# Esp32_with_USBC.net
KiCad netlist of a schematic drawn in Altium Designer
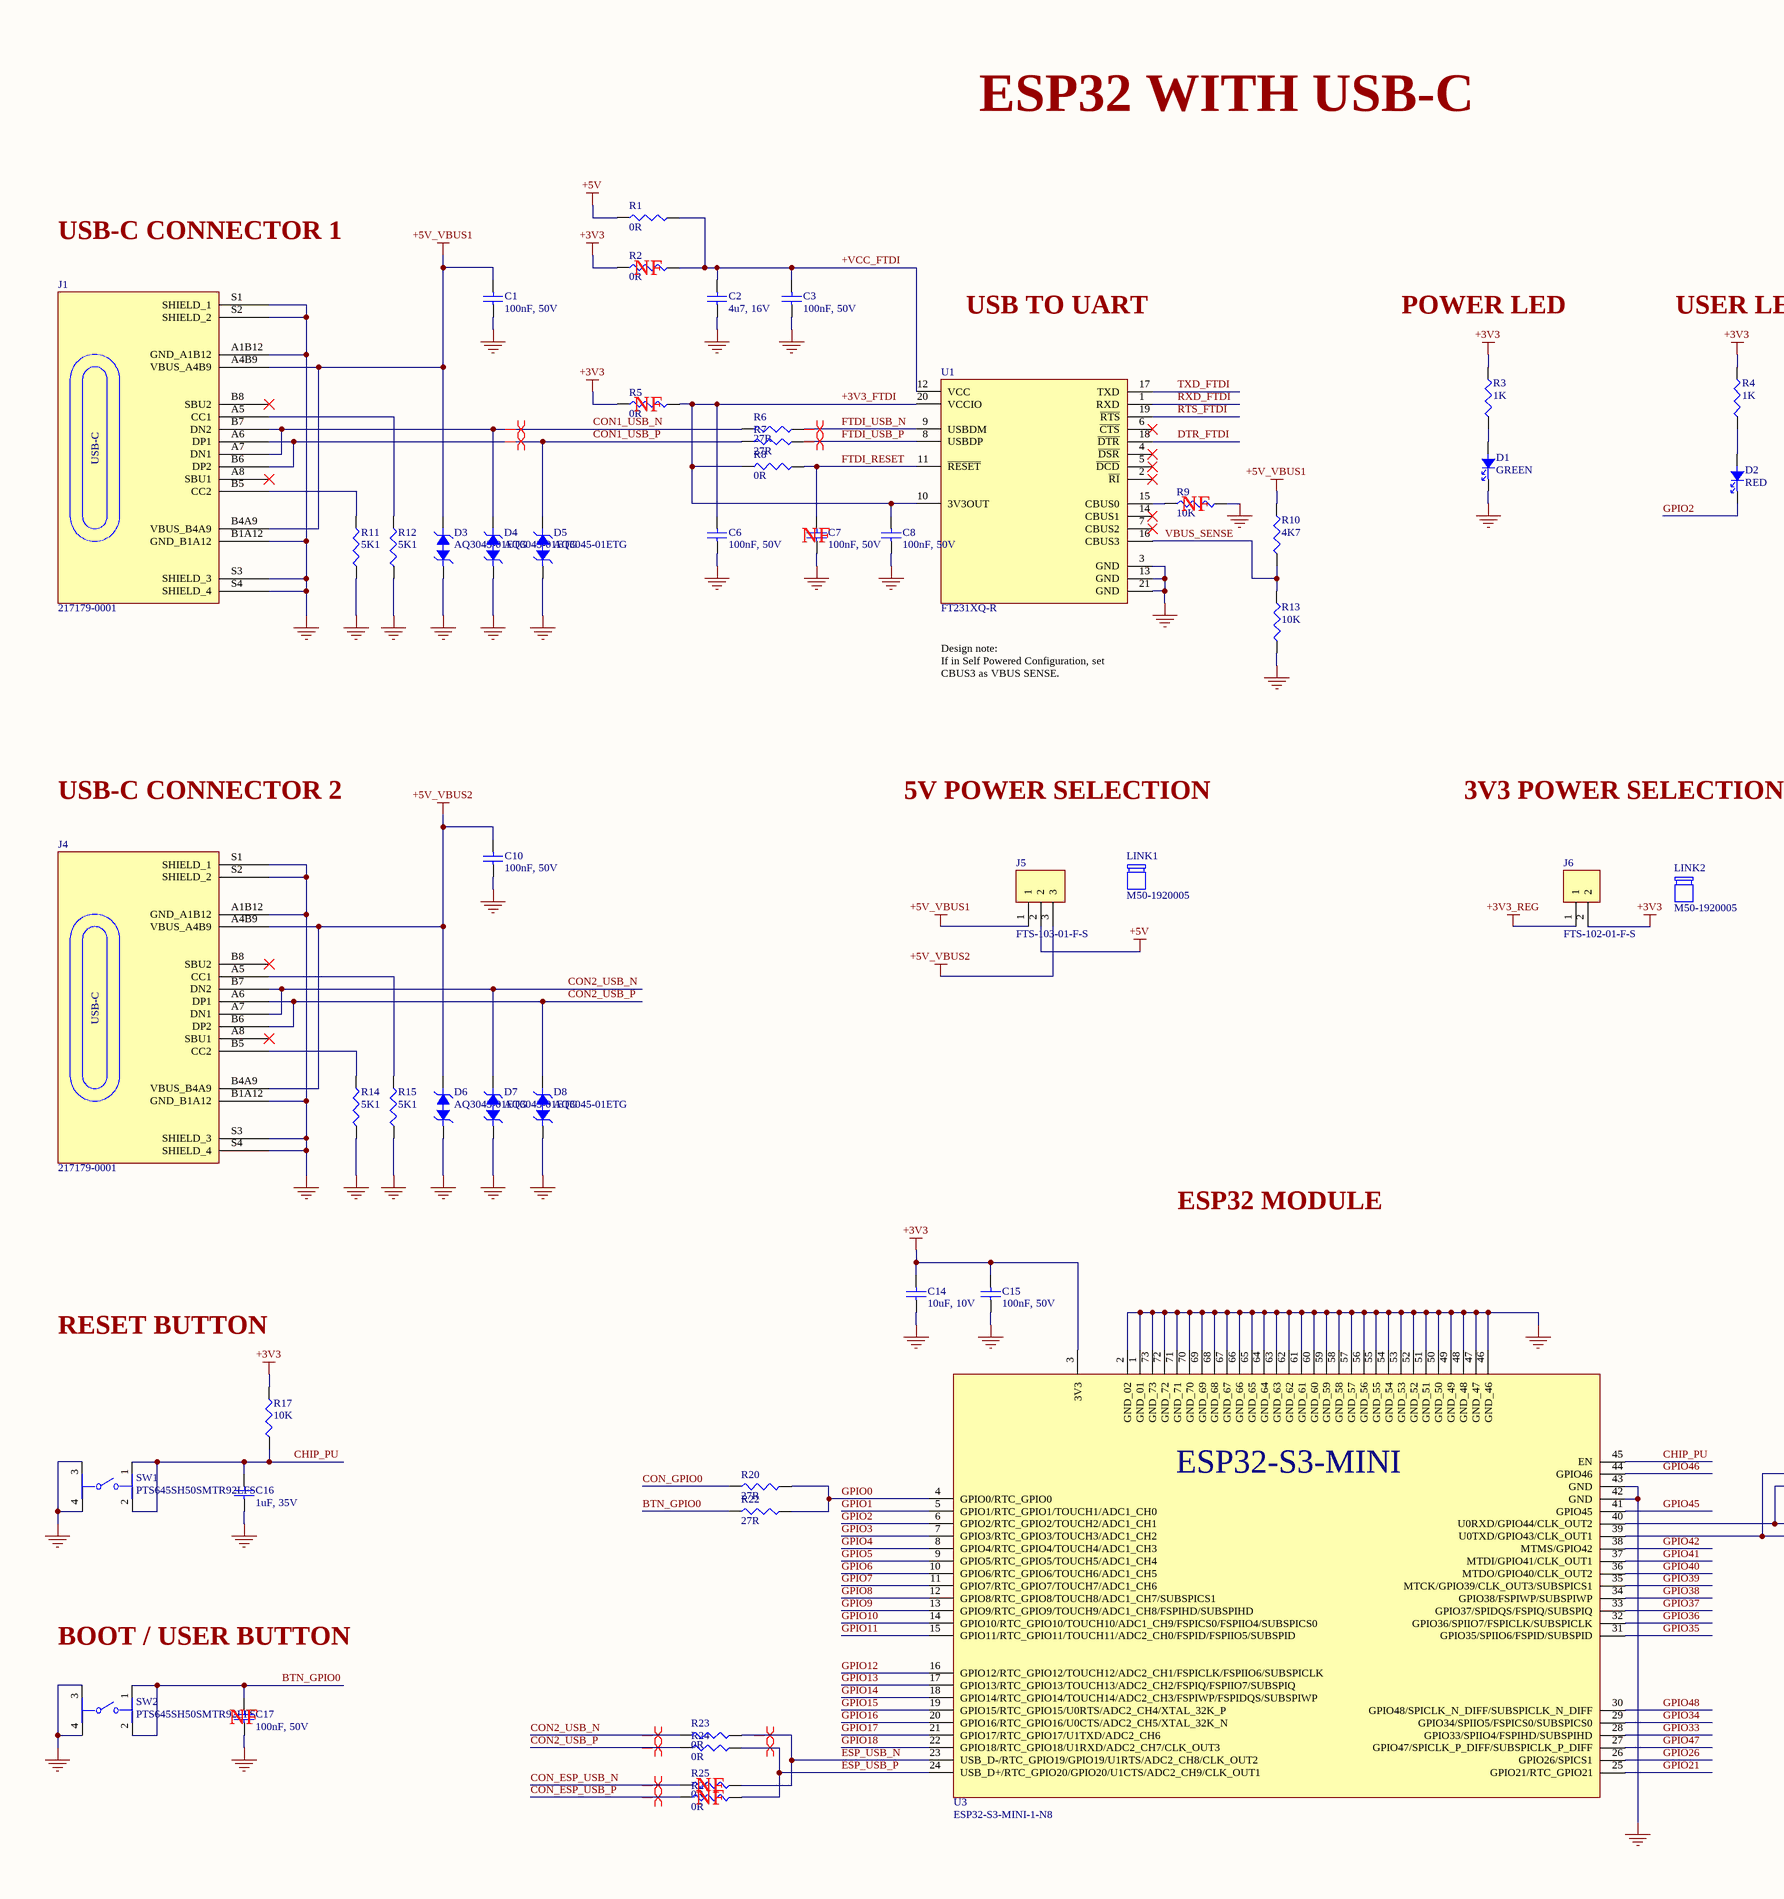
[diagram p0: Esp32 with USBC.SchDoc, left]
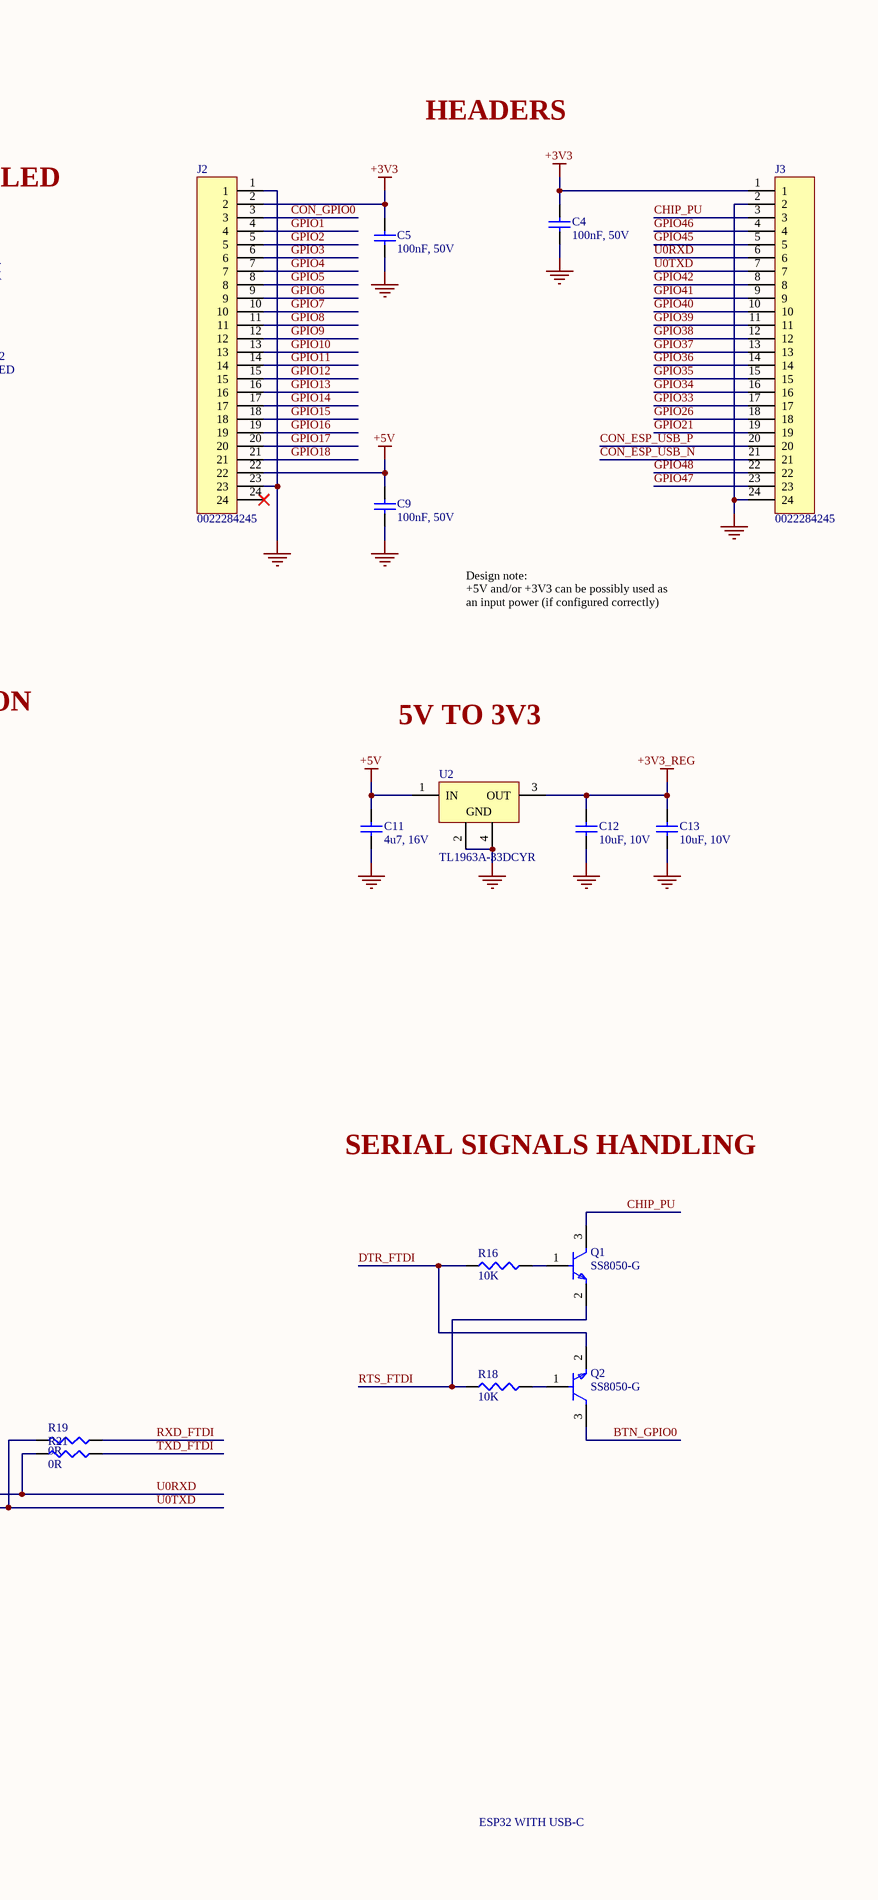
[diagram p1: Esp32 with USBC.SchDoc, right]

(export (version "E")
  (design (tool "Eeschema 10.0.6"))
  (components
    (comp (ref "C1")
      (value "100nF, 50V")
      (footprint "CAPC1005X55N")
      (description "CAP CER 0.1UF 50V X7R 0402")
      (fields
        (field (name "MANUFACTURER") "Samsung")
        (field (name "MANUFACTURER PART NUMBER") "CL05B104KB54PNC")
      )
      (libsource (lib "Schlib") (part "CL05B104KB54PNC"))
    )
    (comp (ref "C2")
      (value "4u7, 16V")
      (footprint "CAPC1005X55N")
      (description "CAP CER 4.7UF 16V X5R 0402")
      (fields
        (field (name "MANUFACTURER") "Samsung")
        (field (name "MANUFACTURER PART NUMBER") "CL05A475MO5NUNC")
      )
      (libsource (lib "Schlib") (part "CL05A475MO5NUNC"))
    )
    (comp (ref "C3")
      (value "100nF, 50V")
      (footprint "CAPC1005X55N")
      (description "CAP CER 0.1UF 50V X7R 0402")
      (fields
        (field (name "MANUFACTURER") "Samsung")
        (field (name "MANUFACTURER PART NUMBER") "CL05B104KB54PNC")
      )
      (libsource (lib "Schlib") (part "CL05B104KB54PNC"))
    )
    (comp (ref "C4")
      (value "100nF, 50V")
      (footprint "CAPC1005X55N")
      (description "CAP CER 0.1UF 50V X7R 0402")
      (fields
        (field (name "MANUFACTURER") "Samsung")
        (field (name "MANUFACTURER PART NUMBER") "CL05B104KB54PNC")
      )
      (libsource (lib "Schlib") (part "CL05B104KB54PNC"))
    )
    (comp (ref "C5")
      (value "100nF, 50V")
      (footprint "CAPC1005X55N")
      (description "CAP CER 0.1UF 50V X7R 0402")
      (fields
        (field (name "MANUFACTURER") "Samsung")
        (field (name "MANUFACTURER PART NUMBER") "CL05B104KB54PNC")
      )
      (libsource (lib "Schlib") (part "CL05B104KB54PNC"))
    )
    (comp (ref "C6")
      (value "100nF, 50V")
      (footprint "CAPC1005X55N")
      (description "CAP CER 0.1UF 50V X7R 0402")
      (fields
        (field (name "MANUFACTURER") "Samsung")
        (field (name "MANUFACTURER PART NUMBER") "CL05B104KB54PNC")
      )
      (libsource (lib "Schlib") (part "CL05B104KB54PNC"))
    )
    (comp (ref "C7")
      (value "100nF, 50V")
      (footprint "CAPC1005X55N")
      (description "CAP CER 0.1UF 50V X7R 0402")
      (fields
        (field (name "MANUFACTURER") "Samsung")
        (field (name "MANUFACTURER PART NUMBER") "CL05B104KB54PNC")
      )
      (libsource (lib "Schlib") (part "CL05B104KB54PNC"))
    )
    (comp (ref "C8")
      (value "100nF, 50V")
      (footprint "CAPC1005X55N")
      (description "CAP CER 0.1UF 50V X7R 0402")
      (fields
        (field (name "MANUFACTURER") "Samsung")
        (field (name "MANUFACTURER PART NUMBER") "CL05B104KB54PNC")
      )
      (libsource (lib "Schlib") (part "CL05B104KB54PNC"))
    )
    (comp (ref "C9")
      (value "100nF, 50V")
      (footprint "CAPC1005X55N")
      (description "CAP CER 0.1UF 50V X7R 0402")
      (fields
        (field (name "MANUFACTURER") "Samsung")
        (field (name "MANUFACTURER PART NUMBER") "CL05B104KB54PNC")
      )
      (libsource (lib "Schlib") (part "CL05B104KB54PNC"))
    )
    (comp (ref "C10")
      (value "100nF, 50V")
      (footprint "CAPC1005X55N")
      (description "CAP CER 0.1UF 50V X7R 0402")
      (fields
        (field (name "MANUFACTURER") "Samsung")
        (field (name "MANUFACTURER PART NUMBER") "CL05B104KB54PNC")
      )
      (libsource (lib "Schlib") (part "CL05B104KB54PNC"))
    )
    (comp (ref "C11")
      (value "4u7, 16V")
      (footprint "CAPC1005X55N")
      (description "CAP CER 4.7UF 16V X5R 0402")
      (fields
        (field (name "MANUFACTURER") "Samsung")
        (field (name "MANUFACTURER PART NUMBER") "CL05A475MO5NUNC")
      )
      (libsource (lib "Schlib") (part "CL05A475MO5NUNC"))
    )
    (comp (ref "C12")
      (value "10uF, 10V")
      (footprint "CAPC1005X55N")
      (description "CAP CER 10UF 10V X5R 0402")
      (fields
        (field (name "MANUFACTURER") "Samsung")
        (field (name "MANUFACTURER PART NUMBER") "CL05A106MP8NUB8")
      )
      (libsource (lib "Schlib") (part "CL05A106MP8NUB8"))
    )
    (comp (ref "C13")
      (value "10uF, 10V")
      (footprint "CAPC1005X55N")
      (description "CAP CER 10UF 10V X5R 0402")
      (fields
        (field (name "MANUFACTURER") "Samsung")
        (field (name "MANUFACTURER PART NUMBER") "CL05A106MP8NUB8")
      )
      (libsource (lib "Schlib") (part "CL05A106MP8NUB8"))
    )
    (comp (ref "C14")
      (value "10uF, 10V")
      (footprint "CAPC1005X55N")
      (description "CAP CER 10UF 10V X5R 0402")
      (fields
        (field (name "MANUFACTURER") "Samsung")
        (field (name "MANUFACTURER PART NUMBER") "CL05A106MP8NUB8")
      )
      (libsource (lib "Schlib") (part "CL05A106MP8NUB8"))
    )
    (comp (ref "C15")
      (value "100nF, 50V")
      (footprint "CAPC1005X55N")
      (description "CAP CER 0.1UF 50V X7R 0402")
      (fields
        (field (name "MANUFACTURER") "Samsung")
        (field (name "MANUFACTURER PART NUMBER") "CL05B104KB54PNC")
      )
      (libsource (lib "Schlib") (part "CL05B104KB54PNC"))
    )
    (comp (ref "C16")
      (value "1uF, 35V")
      (footprint "CAPC1005X55N")
      (description "CAP CER 1UF 35V X5R 0402")
      (fields
        (field (name "MANUFACTURER") "Samsung")
        (field (name "MANUFACTURER PART NUMBER") "CL05A105KL5NRNC")
      )
      (libsource (lib "Schlib") (part "CL05A105KL5NRNC"))
    )
    (comp (ref "C17")
      (value "100nF, 50V")
      (footprint "CAPC1005X55N")
      (description "CAP CER 0.1UF 50V X7R 0402")
      (fields
        (field (name "MANUFACTURER") "Samsung")
        (field (name "MANUFACTURER PART NUMBER") "CL05B104KB54PNC")
      )
      (libsource (lib "Schlib") (part "CL05B104KB54PNC"))
    )
    (comp (ref "D1")
      (value "GREEN")
      (footprint "LED0402G")
      (description "LED YLW-GRN 0402 SMD")
      (fields
        (field (name "MANUFACTURER") "Vishay")
        (field (name "MANUFACTURER PART NUMBER") "VLMG1500-GS08")
      )
      (libsource (lib "Schlib") (part "VLMG1500-GS08"))
    )
    (comp (ref "D2")
      (value "RED")
      (footprint "LED0402R")
      (description "LED RED 0402 SMD")
      (fields
        (field (name "MANUFACTURER") "Vishay")
        (field (name "MANUFACTURER PART NUMBER") "VLMS1500-GS08")
      )
      (libsource (lib "Schlib") (part "VLMS1500-GS08"))
    )
    (comp (ref "D3")
      (value "AQ3045-01ETG")
      (footprint "SOD882")
      (description "TVS DIODE 5.3VWM 12VC SOD882")
      (fields (field (name "MANUFACTURER") "Littelfuse") (field (name "LCSC PART NUMBER") "C3710326"))
      (libsource (lib "Schlib") (part "AQ3045-01ETG"))
    )
    (comp (ref "D4")
      (value "AQ3045-01ETG")
      (footprint "SOD882")
      (description "TVS DIODE 5.3VWM 12VC SOD882")
      (fields (field (name "MANUFACTURER") "Littelfuse") (field (name "LCSC PART NUMBER") "C3710326"))
      (libsource (lib "Schlib") (part "AQ3045-01ETG"))
    )
    (comp (ref "D5")
      (value "AQ3045-01ETG")
      (footprint "SOD882")
      (description "TVS DIODE 5.3VWM 12VC SOD882")
      (fields (field (name "MANUFACTURER") "Littelfuse") (field (name "LCSC PART NUMBER") "C3710326"))
      (libsource (lib "Schlib") (part "AQ3045-01ETG"))
    )
    (comp (ref "D6")
      (value "AQ3045-01ETG")
      (footprint "SOD882")
      (description "TVS DIODE 5.3VWM 12VC SOD882")
      (fields (field (name "MANUFACTURER") "Littelfuse") (field (name "LCSC PART NUMBER") "C3710326"))
      (libsource (lib "Schlib") (part "AQ3045-01ETG"))
    )
    (comp (ref "D7")
      (value "AQ3045-01ETG")
      (footprint "SOD882")
      (description "TVS DIODE 5.3VWM 12VC SOD882")
      (fields (field (name "MANUFACTURER") "Littelfuse") (field (name "LCSC PART NUMBER") "C3710326"))
      (libsource (lib "Schlib") (part "AQ3045-01ETG"))
    )
    (comp (ref "D8")
      (value "AQ3045-01ETG")
      (footprint "SOD882")
      (description "TVS DIODE 5.3VWM 12VC SOD882")
      (fields (field (name "MANUFACTURER") "Littelfuse") (field (name "LCSC PART NUMBER") "C3710326"))
      (libsource (lib "Schlib") (part "AQ3045-01ETG"))
    )
    (comp (ref "J1")
      (value "217179-0001")
      (footprint "FP-2171790001-MFG")
      (description "CONN RCP USB2.0 TYP C 24P SMD RA")
      (fields (field (name "MANUFACTURER") "Molex") (field (name "LCSC PART NUMBER") "C3197684"))
      (libsource (lib "Schlib") (part "217179-0001"))
    )
    (comp (ref "J2")
      (value "0022284245")
      (footprint "HDR_1X24_2.54MM")
      (description "CONN HEADER VERT 24POS 2.54MM")
      (fields (field (name "MANUFACTURER") "Molex") (field (name "LCSC PART NUMBER") "C7145888"))
      (libsource (lib "") (part "0022284245_1"))
    )
    (comp (ref "J3")
      (value "0022284245")
      (footprint "HDR_1X24_2.54MM")
      (description "CONN HEADER VERT 24POS 2.54MM")
      (fields (field (name "MANUFACTURER") "Molex") (field (name "LCSC PART NUMBER") "C7145888"))
      (libsource (lib "Schlib") (part "0022284245"))
    )
    (comp (ref "J4")
      (value "217179-0001")
      (footprint "FP-2171790001-MFG")
      (description "CONN RCP USB2.0 TYP C 24P SMD RA")
      (fields (field (name "MANUFACTURER") "Molex") (field (name "LCSC PART NUMBER") "C3197684"))
      (libsource (lib "Schlib") (part "217179-0001"))
    )
    (comp (ref "J5")
      (value "FTS-103-01-F-S")
      (footprint "HDR_1X3_1.27MM")
      (description "CONN HEADER VERT 3POS 1.27MM")
      (fields (field (name "MANUFACTURER") "Samtec") (field (name "LCSC PART NUMBER") "C3333578"))
      (libsource (lib "Schlib") (part "FTS-103-01-F-S"))
    )
    (comp (ref "J6")
      (value "FTS-102-01-F-S")
      (footprint "HDR_1X2_1.27MM")
      (description "CONN HEADER VERT 2POS 1.27MM")
      (fields (field (name "MANUFACTURER") "Samtec") (field (name "LCSC PART NUMBER") "C6045317"))
      (libsource (lib "Schlib") (part "FTS-102-01-F-S"))
    )
    (comp (ref "LINK1")
      (value "M50-1920005")
      (description "CONN SHUNT 1.27MM RED")
      (fields (field (name "MANUFACTURER") "Harwin") (field (name "LCSC PART NUMBER") "C6985646"))
      (libsource (lib "Schlib") (part "M50-1920005"))
    )
    (comp (ref "LINK2")
      (value "M50-1920005")
      (description "CONN SHUNT 1.27MM RED")
      (fields (field (name "MANUFACTURER") "Harwin") (field (name "LCSC PART NUMBER") "C6985646"))
      (libsource (lib "Schlib") (part "M50-1920005"))
    )
    (comp (ref "Q1")
      (value "SS8050-G")
      (footprint "FP-SS8050-G-IPC_B")
      (description "TRANS NPN 25V 1.5A SOT23-3")
      (fields (field (name "MANUFACTURER") "Comchip") (field (name "LCSC PART NUMBER") "C164886"))
      (libsource (lib "Schlib") (part "SS8050-G"))
    )
    (comp (ref "Q2")
      (value "SS8050-G")
      (footprint "FP-SS8050-G-IPC_B")
      (description "TRANS NPN 25V 1.5A SOT23-3")
      (fields (field (name "MANUFACTURER") "Comchip") (field (name "LCSC PART NUMBER") "C164886"))
      (libsource (lib "Schlib") (part "SS8050-G"))
    )
    (comp (ref "R1")
      (value "0R")
      (footprint "RESC1005X37N")
      (description "RES 0 OHM JUMPER 1/16W 0402")
      (fields
        (field (name "MANUFACTURER") "Yageo")
        (field (name "MANUFACTURER PART NUMBER") "RC0402JR-070RL")
      )
      (libsource (lib "Schlib") (part "RC0402JR-070RL"))
    )
    (comp (ref "R2")
      (value "0R")
      (footprint "RESC1005X37N")
      (description "RES 0 OHM JUMPER 1/16W 0402")
      (fields
        (field (name "MANUFACTURER") "Yageo")
        (field (name "MANUFACTURER PART NUMBER") "RC0402JR-070RL")
      )
      (libsource (lib "Schlib") (part "RC0402JR-070RL"))
    )
    (comp (ref "R3")
      (value "1K")
      (footprint "RESC1005X37N")
      (description "RES 1K OHM 1% 1/16W 0402")
      (fields
        (field (name "MANUFACTURER") "Yageo")
        (field (name "MANUFACTURER PART NUMBER") "RC0402FR-071KL")
      )
      (libsource (lib "Schlib") (part "RC0402FR-071KL"))
    )
    (comp (ref "R4")
      (value "1K")
      (footprint "RESC1005X37N")
      (description "RES 1K OHM 1% 1/16W 0402")
      (fields
        (field (name "MANUFACTURER") "Yageo")
        (field (name "MANUFACTURER PART NUMBER") "RC0402FR-071KL")
      )
      (libsource (lib "Schlib") (part "RC0402FR-071KL"))
    )
    (comp (ref "R5")
      (value "0R")
      (footprint "RESC1005X37N")
      (description "RES 0 OHM JUMPER 1/16W 0402")
      (fields
        (field (name "MANUFACTURER") "Yageo")
        (field (name "MANUFACTURER PART NUMBER") "RC0402JR-070RL")
      )
      (libsource (lib "Schlib") (part "RC0402JR-070RL"))
    )
    (comp (ref "R6")
      (value "27R")
      (footprint "RESC1005X37N")
      (description "RES 27 OHM 1% 1/16W 0402")
      (fields
        (field (name "MANUFACTURER") "Yageo")
        (field (name "MANUFACTURER PART NUMBER") "RC0402FR-0727RL")
      )
      (libsource (lib "Schlib") (part "RC0402FR-0727RL"))
    )
    (comp (ref "R7")
      (value "27R")
      (footprint "RESC1005X37N")
      (description "RES 27 OHM 1% 1/16W 0402")
      (fields
        (field (name "MANUFACTURER") "Yageo")
        (field (name "MANUFACTURER PART NUMBER") "RC0402FR-0727RL")
      )
      (libsource (lib "Schlib") (part "RC0402FR-0727RL"))
    )
    (comp (ref "R8")
      (value "0R")
      (footprint "RESC1005X37N")
      (description "RES 0 OHM JUMPER 1/16W 0402")
      (fields
        (field (name "MANUFACTURER") "Yageo")
        (field (name "MANUFACTURER PART NUMBER") "RC0402JR-070RL")
      )
      (libsource (lib "Schlib") (part "RC0402JR-070RL"))
    )
    (comp (ref "R9")
      (value "10K")
      (footprint "RESC1005X37N")
      (description "RES SMD 10K OHM 1% 1/16W 0402")
      (fields
        (field (name "MANUFACTURER") "Yageo")
        (field (name "MANUFACTURER PART NUMBER") "AC0402FR-0710KL")
      )
      (libsource (lib "Schlib") (part "AC0402FR-0710KL"))
    )
    (comp (ref "R10")
      (value "4K7")
      (footprint "RESC1005X37N")
      (description "RES 4.7K OHM 1% 1/16W 0402")
      (fields
        (field (name "MANUFACTURER") "Yageo")
        (field (name "MANUFACTURER PART NUMBER") "RC0402FR-074K7L")
      )
      (libsource (lib "Schlib") (part "RC0402FR-074K7L"))
    )
    (comp (ref "R11")
      (value "5K1")
      (footprint "RESC1005X37N")
      (description "RES SMD 5.1K OHM 1% 1/16W 0402")
      (fields
        (field (name "MANUFACTURER") "Yageo")
        (field (name "MANUFACTURER PART NUMBER") "AC0402FR-075K1L")
      )
      (libsource (lib "Schlib") (part "AC0402FR-075K1L"))
    )
    (comp (ref "R12")
      (value "5K1")
      (footprint "RESC1005X37N")
      (description "RES SMD 5.1K OHM 1% 1/16W 0402")
      (fields
        (field (name "MANUFACTURER") "Yageo")
        (field (name "MANUFACTURER PART NUMBER") "AC0402FR-075K1L")
      )
      (libsource (lib "Schlib") (part "AC0402FR-075K1L"))
    )
    (comp (ref "R13")
      (value "10K")
      (footprint "RESC1005X37N")
      (description "RES SMD 10K OHM 1% 1/16W 0402")
      (fields
        (field (name "MANUFACTURER") "Yageo")
        (field (name "MANUFACTURER PART NUMBER") "AC0402FR-0710KL")
      )
      (libsource (lib "Schlib") (part "AC0402FR-0710KL"))
    )
    (comp (ref "R14")
      (value "5K1")
      (footprint "RESC1005X37N")
      (description "RES SMD 5.1K OHM 1% 1/16W 0402")
      (fields
        (field (name "MANUFACTURER") "Yageo")
        (field (name "MANUFACTURER PART NUMBER") "AC0402FR-075K1L")
      )
      (libsource (lib "Schlib") (part "AC0402FR-075K1L"))
    )
    (comp (ref "R15")
      (value "5K1")
      (footprint "RESC1005X37N")
      (description "RES SMD 5.1K OHM 1% 1/16W 0402")
      (fields
        (field (name "MANUFACTURER") "Yageo")
        (field (name "MANUFACTURER PART NUMBER") "AC0402FR-075K1L")
      )
      (libsource (lib "Schlib") (part "AC0402FR-075K1L"))
    )
    (comp (ref "R16")
      (value "10K")
      (footprint "RESC1005X37N")
      (description "RES SMD 10K OHM 1% 1/16W 0402")
      (fields
        (field (name "MANUFACTURER") "Yageo")
        (field (name "MANUFACTURER PART NUMBER") "AC0402FR-0710KL")
      )
      (libsource (lib "Schlib") (part "AC0402FR-0710KL"))
    )
    (comp (ref "R17")
      (value "10K")
      (footprint "RESC1005X37N")
      (description "RES SMD 10K OHM 1% 1/16W 0402")
      (fields
        (field (name "MANUFACTURER") "Yageo")
        (field (name "MANUFACTURER PART NUMBER") "AC0402FR-0710KL")
      )
      (libsource (lib "Schlib") (part "AC0402FR-0710KL"))
    )
    (comp (ref "R18")
      (value "10K")
      (footprint "RESC1005X37N")
      (description "RES SMD 10K OHM 1% 1/16W 0402")
      (fields
        (field (name "MANUFACTURER") "Yageo")
        (field (name "MANUFACTURER PART NUMBER") "AC0402FR-0710KL")
      )
      (libsource (lib "Schlib") (part "AC0402FR-0710KL"))
    )
    (comp (ref "R19")
      (value "0R")
      (footprint "RESC1005X37N")
      (description "RES 0 OHM JUMPER 1/16W 0402")
      (fields
        (field (name "MANUFACTURER") "Yageo")
        (field (name "MANUFACTURER PART NUMBER") "RC0402JR-070RL")
      )
      (libsource (lib "Schlib") (part "RC0402JR-070RL"))
    )
    (comp (ref "R20")
      (value "27R")
      (footprint "RESC1005X37N")
      (description "RES 27 OHM 1% 1/16W 0402")
      (fields
        (field (name "MANUFACTURER") "Yageo")
        (field (name "MANUFACTURER PART NUMBER") "RC0402FR-0727RL")
      )
      (libsource (lib "Schlib") (part "RC0402FR-0727RL"))
    )
    (comp (ref "R21")
      (value "0R")
      (footprint "RESC1005X37N")
      (description "RES 0 OHM JUMPER 1/16W 0402")
      (fields
        (field (name "MANUFACTURER") "Yageo")
        (field (name "MANUFACTURER PART NUMBER") "RC0402JR-070RL")
      )
      (libsource (lib "Schlib") (part "RC0402JR-070RL"))
    )
    (comp (ref "R22")
      (value "27R")
      (footprint "RESC1005X37N")
      (description "RES 27 OHM 1% 1/16W 0402")
      (fields
        (field (name "MANUFACTURER") "Yageo")
        (field (name "MANUFACTURER PART NUMBER") "RC0402FR-0727RL")
      )
      (libsource (lib "Schlib") (part "RC0402FR-0727RL"))
    )
    (comp (ref "R23")
      (value "0R")
      (footprint "RESC1005X37N")
      (description "RES 0 OHM JUMPER 1/16W 0402")
      (fields
        (field (name "MANUFACTURER") "Yageo")
        (field (name "MANUFACTURER PART NUMBER") "RC0402JR-070RL")
      )
      (libsource (lib "Schlib") (part "RC0402JR-070RL"))
    )
    (comp (ref "R24")
      (value "0R")
      (footprint "RESC1005X37N")
      (description "RES 0 OHM JUMPER 1/16W 0402")
      (fields
        (field (name "MANUFACTURER") "Yageo")
        (field (name "MANUFACTURER PART NUMBER") "RC0402JR-070RL")
      )
      (libsource (lib "Schlib") (part "RC0402JR-070RL"))
    )
    (comp (ref "R25")
      (value "0R")
      (footprint "RESC1005X37N")
      (description "RES 0 OHM JUMPER 1/16W 0402")
      (fields
        (field (name "MANUFACTURER") "Yageo")
        (field (name "MANUFACTURER PART NUMBER") "RC0402JR-070RL")
      )
      (libsource (lib "Schlib") (part "RC0402JR-070RL"))
    )
    (comp (ref "R26")
      (value "0R")
      (footprint "RESC1005X37N")
      (description "RES 0 OHM JUMPER 1/16W 0402")
      (fields
        (field (name "MANUFACTURER") "Yageo")
        (field (name "MANUFACTURER PART NUMBER") "RC0402JR-070RL")
      )
      (libsource (lib "Schlib") (part "RC0402JR-070RL"))
    )
    (comp (ref "SW1")
      (value "PTS645SH50SMTR92LFS")
      (footprint "FP-PTS645SH50SMTR92LFS-MFG")
      (description "SWITCH TACTILE SPST-NO 0.05A 12V")
      (fields (field (name "MANUFACTURER") "ITT C&K") (field (name "LCSC PART NUMBER") "C221869"))
      (libsource (lib "Schlib") (part "PTS645SH50SMTR92LFS"))
    )
    (comp (ref "SW2")
      (value "PTS645SH50SMTR92LFS")
      (footprint "FP-PTS645SH50SMTR92LFS-MFG")
      (description "SWITCH TACTILE SPST-NO 0.05A 12V")
      (fields (field (name "MANUFACTURER") "ITT C&K") (field (name "LCSC PART NUMBER") "C221869"))
      (libsource (lib "Schlib") (part "PTS645SH50SMTR92LFS"))
    )
    (comp (ref "U1")
      (value "FT231XQ-R")
      (footprint "FP-QFN-20-IPC_B")
      (description "IC USB SERIAL FULL UART 20QFN")
      (fields (field (name "MANUFACTURER") "FTDI") (field (name "LCSC PART NUMBER") "C132159"))
      (libsource (lib "Schlib") (part "FT231XQ-R"))
    )
    (comp (ref "U2")
      (value "TL1963A-33DCYR")
      (footprint "DCY0004A_N")
      (description "IC REG LINEAR 3.3V 1.5A SOT223-4")
      (fields (field (name "MANUFACTURER") "Texas Instruments") (field (name "LCSC PART NUMBER") "C181262"))
      (libsource (lib "Schlib") (part "TL1963A-33DCYR"))
    )
    (comp (ref "U3")
      (value "ESP32-S3-MINI-1-N8")
      (footprint "XCVR_ESP32-S3-MINI-1-N8")
      (description "SMD Module, ESP32-S3FN8, 8 mb Sp")
      (fields (field (name "MANUFACTURER") "Espressif Systems") (field (name "LCSC PART NUMBER") "C2913206"))
      (libsource (lib "Schlib") (part "ESP32-S3-MINI-1-N8"))
    )
  )
  (nets
    (net (code "1") (name "+3V3") (class "Default")
      (node (ref "C14") (pin "2") (pinfunction "2_2") (pintype "passive"))
      (node (ref "C15") (pin "2") (pinfunction "2_2") (pintype "passive"))
      (node (ref "C4") (pin "2") (pinfunction "2_2") (pintype "passive"))
      (node (ref "C5") (pin "2") (pinfunction "2_2") (pintype "passive"))
      (node (ref "J2") (pin "2") (pinfunction "2_2") (pintype "passive"))
      (node (ref "J3") (pin "1") (pinfunction "1_1") (pintype "passive"))
      (node (ref "J6") (pin "2") (pinfunction "2_2") (pintype "passive"))
      (node (ref "R17") (pin "2") (pinfunction "2_2") (pintype "passive"))
      (node (ref "R2") (pin "1") (pinfunction "1_1") (pintype "passive"))
      (node (ref "R3") (pin "2") (pinfunction "2_2") (pintype "passive"))
      (node (ref "R4") (pin "2") (pinfunction "2_2") (pintype "passive"))
      (node (ref "R5") (pin "1") (pinfunction "1_1") (pintype "passive"))
      (node (ref "U3") (pin "3") (pinfunction "3V3_3") (pintype "passive"))
    )
    (net (code "2") (name "+3V3_REG") (class "Default")
      (node (ref "C12") (pin "2") (pinfunction "2_2") (pintype "passive"))
      (node (ref "C13") (pin "2") (pinfunction "2_2") (pintype "passive"))
      (node (ref "J6") (pin "1") (pinfunction "1_1") (pintype "passive"))
      (node (ref "U2") (pin "3") (pinfunction "OUT_3") (pintype "power_in"))
    )
    (net (code "3") (name "+5V") (class "Default")
      (node (ref "C11") (pin "2") (pinfunction "2_2") (pintype "passive"))
      (node (ref "C9") (pin "2") (pinfunction "2_2") (pintype "passive"))
      (node (ref "J2") (pin "22") (pinfunction "22_22") (pintype "passive"))
      (node (ref "J5") (pin "2") (pinfunction "2_2") (pintype "passive"))
      (node (ref "R1") (pin "1") (pinfunction "1_1") (pintype "passive"))
      (node (ref "U2") (pin "1") (pinfunction "IN_1") (pintype "power_in"))
    )
    (net (code "4") (name "+5V_VBUS1") (class "Default")
      (node (ref "C1") (pin "2") (pinfunction "2_2") (pintype "passive"))
      (node (ref "D3") (pin "2") (pinfunction "2_2") (pintype "passive"))
      (node (ref "J1") (pin "A4B9") (pinfunction "VBUS_A4B9_A4B9") (pintype "passive"))
      (node (ref "J1") (pin "B4A9") (pinfunction "VBUS_B4A9_B4A9") (pintype "passive"))
      (node (ref "J5") (pin "1") (pinfunction "1_1") (pintype "passive"))
      (node (ref "R10") (pin "2") (pinfunction "2_2") (pintype "passive"))
    )
    (net (code "5") (name "+5V_VBUS2") (class "Default")
      (node (ref "C10") (pin "2") (pinfunction "2_2") (pintype "passive"))
      (node (ref "D6") (pin "2") (pinfunction "2_2") (pintype "passive"))
      (node (ref "J4") (pin "A4B9") (pinfunction "VBUS_A4B9_A4B9") (pintype "passive"))
      (node (ref "J4") (pin "B4A9") (pinfunction "VBUS_B4A9_B4A9") (pintype "passive"))
      (node (ref "J5") (pin "3") (pinfunction "3_3") (pintype "passive"))
    )
    (net (code "6") (name "/+3V3_FTDI") (class "Default")
      (node (ref "C6") (pin "2") (pinfunction "2_2") (pintype "passive"))
      (node (ref "C8") (pin "2") (pinfunction "2_2") (pintype "passive"))
      (node (ref "R5") (pin "2") (pinfunction "2_2") (pintype "passive"))
      (node (ref "R8") (pin "1") (pinfunction "1_1") (pintype "passive"))
      (node (ref "U1") (pin "10") (pinfunction "3V3OUT_10") (pintype "passive"))
      (node (ref "U1") (pin "20") (pinfunction "VCCIO_20") (pintype "passive"))
    )
    (net (code "7") (name "/+VCC_FTDI") (class "Default")
      (node (ref "C2") (pin "2") (pinfunction "2_2") (pintype "passive"))
      (node (ref "C3") (pin "2") (pinfunction "2_2") (pintype "passive"))
      (node (ref "R1") (pin "2") (pinfunction "2_2") (pintype "passive"))
      (node (ref "R2") (pin "2") (pinfunction "2_2") (pintype "passive"))
      (node (ref "U1") (pin "12") (pinfunction "VCC_12") (pintype "passive"))
    )
    (net (code "8") (name "/BTN_GPIO0") (class "Default")
      (node (ref "C17") (pin "2") (pinfunction "2_2") (pintype "passive"))
      (node (ref "Q2") (pin "3") (pinfunction "C_3") (pintype "passive"))
      (node (ref "R22") (pin "1") (pinfunction "1_1") (pintype "passive"))
      (node (ref "SW2") (pin "1") (pinfunction "1_1") (pintype "passive"))
      (node (ref "SW2") (pin "2") (pinfunction "2_2") (pintype "passive"))
    )
    (net (code "9") (name "/CHIP_PU") (class "Default")
      (node (ref "C16") (pin "2") (pinfunction "2_2") (pintype "passive"))
      (node (ref "J3") (pin "3") (pinfunction "3_3") (pintype "passive"))
      (node (ref "Q1") (pin "3") (pinfunction "C_3") (pintype "passive"))
      (node (ref "R17") (pin "1") (pinfunction "1_1") (pintype "passive"))
      (node (ref "SW1") (pin "1") (pinfunction "1_1") (pintype "passive"))
      (node (ref "SW1") (pin "2") (pinfunction "2_2") (pintype "passive"))
      (node (ref "U3") (pin "45") (pinfunction "EN_45") (pintype "passive"))
    )
    (net (code "10") (name "/CON1_USB_N") (class "Default")
      (node (ref "D4") (pin "2") (pinfunction "2_2") (pintype "passive"))
      (node (ref "J1") (pin "A7") (pinfunction "DN1_A7") (pintype "passive"))
      (node (ref "J1") (pin "B7") (pinfunction "DN2_B7") (pintype "passive"))
      (node (ref "R6") (pin "1") (pinfunction "1_1") (pintype "passive"))
    )
    (net (code "11") (name "/CON1_USB_P") (class "Default")
      (node (ref "D5") (pin "2") (pinfunction "2_2") (pintype "passive"))
      (node (ref "J1") (pin "A6") (pinfunction "DP1_A6") (pintype "passive"))
      (node (ref "J1") (pin "B6") (pinfunction "DP2_B6") (pintype "passive"))
      (node (ref "R7") (pin "1") (pinfunction "1_1") (pintype "passive"))
    )
    (net (code "12") (name "/CON2_USB_N") (class "Default")
      (node (ref "D7") (pin "2") (pinfunction "2_2") (pintype "passive"))
      (node (ref "J4") (pin "A7") (pinfunction "DN1_A7") (pintype "passive"))
      (node (ref "J4") (pin "B7") (pinfunction "DN2_B7") (pintype "passive"))
      (node (ref "R23") (pin "1") (pinfunction "1_1") (pintype "passive"))
    )
    (net (code "13") (name "/CON2_USB_P") (class "Default")
      (node (ref "D8") (pin "2") (pinfunction "2_2") (pintype "passive"))
      (node (ref "J4") (pin "A6") (pinfunction "DP1_A6") (pintype "passive"))
      (node (ref "J4") (pin "B6") (pinfunction "DP2_B6") (pintype "passive"))
      (node (ref "R24") (pin "1") (pinfunction "1_1") (pintype "passive"))
    )
    (net (code "14") (name "/CON_ESP_USB_N") (class "Default")
      (node (ref "J3") (pin "21") (pinfunction "21_21") (pintype "passive"))
      (node (ref "R25") (pin "1") (pinfunction "1_1") (pintype "passive"))
    )
    (net (code "15") (name "/CON_ESP_USB_P") (class "Default")
      (node (ref "J3") (pin "20") (pinfunction "20_20") (pintype "passive"))
      (node (ref "R26") (pin "1") (pinfunction "1_1") (pintype "passive"))
    )
    (net (code "16") (name "/CON_GPIO0") (class "Default")
      (node (ref "J2") (pin "3") (pinfunction "3_3") (pintype "passive"))
      (node (ref "R20") (pin "1") (pinfunction "1_1") (pintype "passive"))
    )
    (net (code "17") (name "/DTR_FTDI") (class "Default")
      (node (ref "Q2") (pin "2") (pinfunction "E_2") (pintype "passive"))
      (node (ref "R16") (pin "1") (pinfunction "1_1") (pintype "passive"))
      (node (ref "U1") (pin "18") (pinfunction "~{DTR}_18") (pintype "passive"))
    )
    (net (code "18") (name "/ESP_USB_N") (class "Default")
      (node (ref "R23") (pin "2") (pinfunction "2_2") (pintype "passive"))
      (node (ref "R25") (pin "2") (pinfunction "2_2") (pintype "passive"))
      (node (ref "U3") (pin "23") (pinfunction "USB_D-/RTC_GPIO19/GPIO19/U1RTS/ADC2_CH8/CLK_OUT2_23") (pintype "passive"))
    )
    (net (code "19") (name "/ESP_USB_P") (class "Default")
      (node (ref "R24") (pin "2") (pinfunction "2_2") (pintype "passive"))
      (node (ref "R26") (pin "2") (pinfunction "2_2") (pintype "passive"))
      (node (ref "U3") (pin "24") (pinfunction "USB_D+/RTC_GPIO20/GPIO20/U1CTS/ADC2_CH9/CLK_OUT1_24") (pintype "passive"))
    )
    (net (code "20") (name "/FTDI_RESET") (class "Default")
      (node (ref "C7") (pin "2") (pinfunction "2_2") (pintype "passive"))
      (node (ref "R8") (pin "2") (pinfunction "2_2") (pintype "passive"))
      (node (ref "U1") (pin "11") (pinfunction "~{RESET}_11") (pintype "passive"))
    )
    (net (code "21") (name "/FTDI_USB_N") (class "Default")
      (node (ref "R6") (pin "2") (pinfunction "2_2") (pintype "passive"))
      (node (ref "U1") (pin "9") (pinfunction "USBDM_9") (pintype "passive"))
    )
    (net (code "22") (name "/FTDI_USB_P") (class "Default")
      (node (ref "R7") (pin "2") (pinfunction "2_2") (pintype "passive"))
      (node (ref "U1") (pin "8") (pinfunction "USBDP_8") (pintype "passive"))
    )
    (net (code "23") (name "/GPIO0") (class "Default")
      (node (ref "R20") (pin "2") (pinfunction "2_2") (pintype "passive"))
      (node (ref "R22") (pin "2") (pinfunction "2_2") (pintype "passive"))
      (node (ref "U3") (pin "4") (pinfunction "GPIO0/RTC_GPIO0_4") (pintype "passive"))
    )
    (net (code "24") (name "/GPIO1") (class "Default")
      (node (ref "J2") (pin "4") (pinfunction "4_4") (pintype "passive"))
      (node (ref "U3") (pin "5") (pinfunction "GPIO1/RTC_GPIO1/TOUCH1/ADC1_CH0_5") (pintype "passive"))
    )
    (net (code "25") (name "/GPIO2") (class "Default")
      (node (ref "D2") (pin "1") (pinfunction "1_1") (pintype "passive"))
      (node (ref "J2") (pin "5") (pinfunction "5_5") (pintype "passive"))
      (node (ref "U3") (pin "6") (pinfunction "GPIO2/RTC_GPIO2/TOUCH2/ADC1_CH1_6") (pintype "passive"))
    )
    (net (code "26") (name "/GPIO3") (class "Default")
      (node (ref "J2") (pin "6") (pinfunction "6_6") (pintype "passive"))
      (node (ref "U3") (pin "7") (pinfunction "GPIO3/RTC_GPIO3/TOUCH3/ADC1_CH2_7") (pintype "passive"))
    )
    (net (code "27") (name "/GPIO4") (class "Default")
      (node (ref "J2") (pin "7") (pinfunction "7_7") (pintype "passive"))
      (node (ref "U3") (pin "8") (pinfunction "GPIO4/RTC_GPIO4/TOUCH4/ADC1_CH3_8") (pintype "passive"))
    )
    (net (code "28") (name "/GPIO5") (class "Default")
      (node (ref "J2") (pin "8") (pinfunction "8_8") (pintype "passive"))
      (node (ref "U3") (pin "9") (pinfunction "GPIO5/RTC_GPIO5/TOUCH5/ADC1_CH4_9") (pintype "passive"))
    )
    (net (code "29") (name "/GPIO6") (class "Default")
      (node (ref "J2") (pin "9") (pinfunction "9_9") (pintype "passive"))
      (node (ref "U3") (pin "10") (pinfunction "GPIO6/RTC_GPIO6/TOUCH6/ADC1_CH5_10") (pintype "passive"))
    )
    (net (code "30") (name "/GPIO7") (class "Default")
      (node (ref "J2") (pin "10") (pinfunction "10_10") (pintype "passive"))
      (node (ref "U3") (pin "11") (pinfunction "GPIO7/RTC_GPIO7/TOUCH7/ADC1_CH6_11") (pintype "passive"))
    )
    (net (code "31") (name "/GPIO8") (class "Default")
      (node (ref "J2") (pin "11") (pinfunction "11_11") (pintype "passive"))
      (node (ref "U3") (pin "12") (pinfunction "GPIO8/RTC_GPIO8/TOUCH8/ADC1_CH7/SUBSPICS1_12") (pintype "passive"))
    )
    (net (code "32") (name "/GPIO9") (class "Default")
      (node (ref "J2") (pin "12") (pinfunction "12_12") (pintype "passive"))
      (node (ref "U3") (pin "13") (pinfunction "GPIO9/RTC_GPIO9/TOUCH9/ADC1_CH8/FSPIHD/SUBSPIHD_13") (pintype "passive"))
    )
    (net (code "33") (name "/GPIO10") (class "Default")
      (node (ref "J2") (pin "13") (pinfunction "13_13") (pintype "passive"))
      (node (ref "U3") (pin "14") (pinfunction "GPIO10/RTC_GPIO10/TOUCH10/ADC1_CH9/FSPICS0/FSPIIO4/SUBSPICS0_14") (pintype "passive"))
    )
    (net (code "34") (name "/GPIO11") (class "Default")
      (node (ref "J2") (pin "14") (pinfunction "14_14") (pintype "passive"))
      (node (ref "U3") (pin "15") (pinfunction "GPIO11/RTC_GPIO11/TOUCH11/ADC2_CH0/FSPID/FSPIIO5/SUBSPID_15") (pintype "passive"))
    )
    (net (code "35") (name "/GPIO12") (class "Default")
      (node (ref "J2") (pin "15") (pinfunction "15_15") (pintype "passive"))
      (node (ref "U3") (pin "16") (pinfunction "GPIO12/RTC_GPIO12/TOUCH12/ADC2_CH1/FSPICLK/FSPIIO6/SUBSPICLK_16") (pintype "passive"))
    )
    (net (code "36") (name "/GPIO13") (class "Default")
      (node (ref "J2") (pin "16") (pinfunction "16_16") (pintype "passive"))
      (node (ref "U3") (pin "17") (pinfunction "GPIO13/RTC_GPIO13/TOUCH13/ADC2_CH2/FSPIQ/FSPIIO7/SUBSPIQ_17") (pintype "passive"))
    )
    (net (code "37") (name "/GPIO14") (class "Default")
      (node (ref "J2") (pin "17") (pinfunction "17_17") (pintype "passive"))
      (node (ref "U3") (pin "18") (pinfunction "GPIO14/RTC_GPIO14/TOUCH14/ADC2_CH3/FSPIWP/FSPIDQS/SUBSPIWP_18") (pintype "passive"))
    )
    (net (code "38") (name "/GPIO15") (class "Default")
      (node (ref "J2") (pin "18") (pinfunction "18_18") (pintype "passive"))
      (node (ref "U3") (pin "19") (pinfunction "GPIO15/RTC_GPIO15/U0RTS/ADC2_CH4/XTAL_32K_P_19") (pintype "passive"))
    )
    (net (code "39") (name "/GPIO16") (class "Default")
      (node (ref "J2") (pin "19") (pinfunction "19_19") (pintype "passive"))
      (node (ref "U3") (pin "20") (pinfunction "GPIO16/RTC_GPIO16/U0CTS/ADC2_CH5/XTAL_32K_N_20") (pintype "passive"))
    )
    (net (code "40") (name "/GPIO17") (class "Default")
      (node (ref "J2") (pin "20") (pinfunction "20_20") (pintype "passive"))
      (node (ref "U3") (pin "21") (pinfunction "GPIO17/RTC_GPIO17/U1TXD/ADC2_CH6_21") (pintype "passive"))
    )
    (net (code "41") (name "/GPIO18") (class "Default")
      (node (ref "J2") (pin "21") (pinfunction "21_21") (pintype "passive"))
      (node (ref "U3") (pin "22") (pinfunction "GPIO18/RTC_GPIO18/U1RXD/ADC2_CH7/CLK_OUT3_22") (pintype "passive"))
    )
    (net (code "42") (name "/GPIO21") (class "Default")
      (node (ref "J3") (pin "19") (pinfunction "19_19") (pintype "passive"))
      (node (ref "U3") (pin "25") (pinfunction "GPIO21/RTC_GPIO21_25") (pintype "passive"))
    )
    (net (code "43") (name "/GPIO26") (class "Default")
      (node (ref "J3") (pin "18") (pinfunction "18_18") (pintype "passive"))
      (node (ref "U3") (pin "26") (pinfunction "GPIO26/SPICS1_26") (pintype "passive"))
    )
    (net (code "44") (name "/GPIO33") (class "Default")
      (node (ref "J3") (pin "17") (pinfunction "17_17") (pintype "passive"))
      (node (ref "U3") (pin "28") (pinfunction "GPIO33/SPIIO4/FSPIHD/SUBSPIHD_28") (pintype "passive"))
    )
    (net (code "45") (name "/GPIO34") (class "Default")
      (node (ref "J3") (pin "16") (pinfunction "16_16") (pintype "passive"))
      (node (ref "U3") (pin "29") (pinfunction "GPIO34/SPIIO5/FSPICS0/SUBSPICS0_29") (pintype "passive"))
    )
    (net (code "46") (name "/GPIO35") (class "Default")
      (node (ref "J3") (pin "15") (pinfunction "15_15") (pintype "passive"))
      (node (ref "U3") (pin "31") (pinfunction "GPIO35/SPIIO6/FSPID/SUBSPID_31") (pintype "passive"))
    )
    (net (code "47") (name "/GPIO36") (class "Default")
      (node (ref "J3") (pin "14") (pinfunction "14_14") (pintype "passive"))
      (node (ref "U3") (pin "32") (pinfunction "GPIO36/SPIIO7/FSPICLK/SUBSPICLK_32") (pintype "passive"))
    )
    (net (code "48") (name "/GPIO37") (class "Default")
      (node (ref "J3") (pin "13") (pinfunction "13_13") (pintype "passive"))
      (node (ref "U3") (pin "33") (pinfunction "GPIO37/SPIDQS/FSPIQ/SUBSPIQ_33") (pintype "passive"))
    )
    (net (code "49") (name "/GPIO38") (class "Default")
      (node (ref "J3") (pin "12") (pinfunction "12_12") (pintype "passive"))
      (node (ref "U3") (pin "34") (pinfunction "GPIO38/FSPIWP/SUBSPIWP_34") (pintype "passive"))
    )
    (net (code "50") (name "/GPIO39") (class "Default")
      (node (ref "J3") (pin "11") (pinfunction "11_11") (pintype "passive"))
      (node (ref "U3") (pin "35") (pinfunction "MTCK/GPIO39/CLK_OUT3/SUBSPICS1_35") (pintype "passive"))
    )
    (net (code "51") (name "/GPIO40") (class "Default")
      (node (ref "J3") (pin "10") (pinfunction "10_10") (pintype "passive"))
      (node (ref "U3") (pin "36") (pinfunction "MTDO/GPIO40/CLK_OUT2_36") (pintype "passive"))
    )
    (net (code "52") (name "/GPIO41") (class "Default")
      (node (ref "J3") (pin "9") (pinfunction "9_9") (pintype "passive"))
      (node (ref "U3") (pin "37") (pinfunction "MTDI/GPIO41/CLK_OUT1_37") (pintype "passive"))
    )
    (net (code "53") (name "/GPIO42") (class "Default")
      (node (ref "J3") (pin "8") (pinfunction "8_8") (pintype "passive"))
      (node (ref "U3") (pin "38") (pinfunction "MTMS/GPIO42_38") (pintype "passive"))
    )
    (net (code "54") (name "/GPIO45") (class "Default")
      (node (ref "J3") (pin "5") (pinfunction "5_5") (pintype "passive"))
      (node (ref "U3") (pin "41") (pinfunction "GPIO45_41") (pintype "passive"))
    )
    (net (code "55") (name "/GPIO46") (class "Default")
      (node (ref "J3") (pin "4") (pinfunction "4_4") (pintype "passive"))
      (node (ref "U3") (pin "44") (pinfunction "GPIO46_44") (pintype "passive"))
    )
    (net (code "56") (name "/GPIO47") (class "Default")
      (node (ref "J3") (pin "23") (pinfunction "23_23") (pintype "passive"))
      (node (ref "U3") (pin "27") (pinfunction "GPIO47/SPICLK_P_DIFF/SUBSPICLK_P_DIFF_27") (pintype "passive"))
    )
    (net (code "57") (name "/GPIO48") (class "Default")
      (node (ref "J3") (pin "22") (pinfunction "22_22") (pintype "passive"))
      (node (ref "U3") (pin "30") (pinfunction "GPIO48/SPICLK_N_DIFF/SUBSPICLK_N_DIFF_30") (pintype "passive"))
    )
    (net (code "58") (name "/RTS_FTDI") (class "Default")
      (node (ref "Q1") (pin "2") (pinfunction "E_2") (pintype "passive"))
      (node (ref "R18") (pin "1") (pinfunction "1_1") (pintype "passive"))
      (node (ref "U1") (pin "19") (pinfunction "~{RTS}_19") (pintype "passive"))
    )
    (net (code "59") (name "/RXD_FTDI") (class "Default")
      (node (ref "R19") (pin "2") (pinfunction "2_2") (pintype "passive"))
      (node (ref "U1") (pin "1") (pinfunction "RXD_1") (pintype "passive"))
    )
    (net (code "60") (name "/TXD_FTDI") (class "Default")
      (node (ref "R21") (pin "2") (pinfunction "2_2") (pintype "passive"))
      (node (ref "U1") (pin "17") (pinfunction "TXD_17") (pintype "passive"))
    )
    (net (code "61") (name "/U0RXD") (class "Default")
      (node (ref "J3") (pin "6") (pinfunction "6_6") (pintype "passive"))
      (node (ref "R21") (pin "1") (pinfunction "1_1") (pintype "passive"))
      (node (ref "U3") (pin "40") (pinfunction "U0RXD/GPIO44/CLK_OUT2_40") (pintype "passive"))
    )
    (net (code "62") (name "/U0TXD") (class "Default")
      (node (ref "J3") (pin "7") (pinfunction "7_7") (pintype "passive"))
      (node (ref "R19") (pin "1") (pinfunction "1_1") (pintype "passive"))
      (node (ref "U3") (pin "39") (pinfunction "U0TXD/GPIO43/CLK_OUT1_39") (pintype "passive"))
    )
    (net (code "63") (name "/VBUS_SENSE") (class "Default")
      (node (ref "R10") (pin "1") (pinfunction "1_1") (pintype "passive"))
      (node (ref "R13") (pin "1") (pinfunction "1_1") (pintype "passive"))
      (node (ref "U1") (pin "16") (pinfunction "CBUS3_16") (pintype "passive"))
    )
    (net (code "64") (name "GND") (class "Default")
      (node (ref "C1") (pin "1") (pinfunction "1_1") (pintype "passive"))
      (node (ref "C10") (pin "1") (pinfunction "1_1") (pintype "passive"))
      (node (ref "C11") (pin "1") (pinfunction "1_1") (pintype "passive"))
      (node (ref "C12") (pin "1") (pinfunction "1_1") (pintype "passive"))
      (node (ref "C13") (pin "1") (pinfunction "1_1") (pintype "passive"))
      (node (ref "C14") (pin "1") (pinfunction "1_1") (pintype "passive"))
      (node (ref "C15") (pin "1") (pinfunction "1_1") (pintype "passive"))
      (node (ref "C16") (pin "1") (pinfunction "1_1") (pintype "passive"))
      (node (ref "C17") (pin "1") (pinfunction "1_1") (pintype "passive"))
      (node (ref "C2") (pin "1") (pinfunction "1_1") (pintype "passive"))
      (node (ref "C3") (pin "1") (pinfunction "1_1") (pintype "passive"))
      (node (ref "C4") (pin "1") (pinfunction "1_1") (pintype "passive"))
      (node (ref "C5") (pin "1") (pinfunction "1_1") (pintype "passive"))
      (node (ref "C6") (pin "1") (pinfunction "1_1") (pintype "passive"))
      (node (ref "C7") (pin "1") (pinfunction "1_1") (pintype "passive"))
      (node (ref "C8") (pin "1") (pinfunction "1_1") (pintype "passive"))
      (node (ref "C9") (pin "1") (pinfunction "1_1") (pintype "passive"))
      (node (ref "D1") (pin "1") (pinfunction "1_1") (pintype "passive"))
      (node (ref "D3") (pin "1") (pinfunction "1_1") (pintype "passive"))
      (node (ref "D4") (pin "1") (pinfunction "1_1") (pintype "passive"))
      (node (ref "D5") (pin "1") (pinfunction "1_1") (pintype "passive"))
      (node (ref "D6") (pin "1") (pinfunction "1_1") (pintype "passive"))
      (node (ref "D7") (pin "1") (pinfunction "1_1") (pintype "passive"))
      (node (ref "D8") (pin "1") (pinfunction "1_1") (pintype "passive"))
      (node (ref "J1") (pin "A1B12") (pinfunction "GND_A1B12_A1B12") (pintype "passive"))
      (node (ref "J1") (pin "B1A12") (pinfunction "GND_B1A12_B1A12") (pintype "passive"))
      (node (ref "J1") (pin "S1") (pinfunction "SHIELD_1_S1") (pintype "passive"))
      (node (ref "J1") (pin "S2") (pinfunction "SHIELD_2_S2") (pintype "passive"))
      (node (ref "J1") (pin "S3") (pinfunction "SHIELD_3_S3") (pintype "passive"))
      (node (ref "J1") (pin "S4") (pinfunction "SHIELD_4_S4") (pintype "passive"))
      (node (ref "J2") (pin "1") (pinfunction "1_1") (pintype "passive"))
      (node (ref "J2") (pin "23") (pinfunction "23_23") (pintype "passive"))
      (node (ref "J3") (pin "2") (pinfunction "2_2") (pintype "passive"))
      (node (ref "J3") (pin "24") (pinfunction "24_24") (pintype "passive"))
      (node (ref "J4") (pin "A1B12") (pinfunction "GND_A1B12_A1B12") (pintype "passive"))
      (node (ref "J4") (pin "B1A12") (pinfunction "GND_B1A12_B1A12") (pintype "passive"))
      (node (ref "J4") (pin "S1") (pinfunction "SHIELD_1_S1") (pintype "passive"))
      (node (ref "J4") (pin "S2") (pinfunction "SHIELD_2_S2") (pintype "passive"))
      (node (ref "J4") (pin "S3") (pinfunction "SHIELD_3_S3") (pintype "passive"))
      (node (ref "J4") (pin "S4") (pinfunction "SHIELD_4_S4") (pintype "passive"))
      (node (ref "R11") (pin "1") (pinfunction "1_1") (pintype "passive"))
      (node (ref "R12") (pin "1") (pinfunction "1_1") (pintype "passive"))
      (node (ref "R13") (pin "2") (pinfunction "2_2") (pintype "passive"))
      (node (ref "R14") (pin "1") (pinfunction "1_1") (pintype "passive"))
      (node (ref "R15") (pin "1") (pinfunction "1_1") (pintype "passive"))
      (node (ref "R9") (pin "2") (pinfunction "2_2") (pintype "passive"))
      (node (ref "SW1") (pin "3") (pinfunction "3_3") (pintype "passive"))
      (node (ref "SW1") (pin "4") (pinfunction "4_4") (pintype "passive"))
      (node (ref "SW2") (pin "3") (pinfunction "3_3") (pintype "passive"))
      (node (ref "SW2") (pin "4") (pinfunction "4_4") (pintype "passive"))
      (node (ref "U1") (pin "13") (pinfunction "GND_13") (pintype "passive"))
      (node (ref "U1") (pin "21") (pinfunction "GND_21") (pintype "passive"))
      (node (ref "U1") (pin "3") (pinfunction "GND_3") (pintype "passive"))
      (node (ref "U2") (pin "2") (pinfunction "GND_2") (pintype "power_in"))
      (node (ref "U2") (pin "4") (pinfunction "GND_4") (pintype "power_in"))
      (node (ref "U3") (pin "1") (pinfunction "GND_01_1") (pintype "passive"))
      (node (ref "U3") (pin "2") (pinfunction "GND_02_2") (pintype "passive"))
      (node (ref "U3") (pin "42") (pinfunction "GND_42") (pintype "passive"))
      (node (ref "U3") (pin "43") (pinfunction "GND_43") (pintype "passive"))
      (node (ref "U3") (pin "46") (pinfunction "GND_46_46") (pintype "passive"))
      (node (ref "U3") (pin "47") (pinfunction "GND_47_47") (pintype "passive"))
      (node (ref "U3") (pin "48") (pinfunction "GND_48_48") (pintype "passive"))
      (node (ref "U3") (pin "49") (pinfunction "GND_49_49") (pintype "passive"))
      (node (ref "U3") (pin "50") (pinfunction "GND_50_50") (pintype "passive"))
      (node (ref "U3") (pin "51") (pinfunction "GND_51_51") (pintype "passive"))
      (node (ref "U3") (pin "52") (pinfunction "GND_52_52") (pintype "passive"))
      (node (ref "U3") (pin "53") (pinfunction "GND_53_53") (pintype "passive"))
      (node (ref "U3") (pin "54") (pinfunction "GND_54_54") (pintype "passive"))
      (node (ref "U3") (pin "55") (pinfunction "GND_55_55") (pintype "passive"))
      (node (ref "U3") (pin "56") (pinfunction "GND_56_56") (pintype "passive"))
      (node (ref "U3") (pin "57") (pinfunction "GND_57_57") (pintype "passive"))
      (node (ref "U3") (pin "58") (pinfunction "GND_58_58") (pintype "passive"))
      (node (ref "U3") (pin "59") (pinfunction "GND_59_59") (pintype "passive"))
      (node (ref "U3") (pin "60") (pinfunction "GND_60_60") (pintype "passive"))
      (node (ref "U3") (pin "61") (pinfunction "GND_61_61") (pintype "passive"))
      (node (ref "U3") (pin "62") (pinfunction "GND_62_62") (pintype "passive"))
      (node (ref "U3") (pin "63") (pinfunction "GND_63_63") (pintype "passive"))
      (node (ref "U3") (pin "64") (pinfunction "GND_64_64") (pintype "passive"))
      (node (ref "U3") (pin "65") (pinfunction "GND_65_65") (pintype "passive"))
      (node (ref "U3") (pin "66") (pinfunction "GND_66_66") (pintype "passive"))
      (node (ref "U3") (pin "67") (pinfunction "GND_67_67") (pintype "passive"))
      (node (ref "U3") (pin "68") (pinfunction "GND_68_68") (pintype "passive"))
      (node (ref "U3") (pin "69") (pinfunction "GND_69_69") (pintype "passive"))
      (node (ref "U3") (pin "70") (pinfunction "GND_70_70") (pintype "passive"))
      (node (ref "U3") (pin "71") (pinfunction "GND_71_71") (pintype "passive"))
      (node (ref "U3") (pin "72") (pinfunction "GND_72_72") (pintype "passive"))
      (node (ref "U3") (pin "73") (pinfunction "GND_73_73") (pintype "passive"))
    )
    (net (code "65") (name "Net-(D1-Pad2)") (class "Default")
      (node (ref "D1") (pin "2") (pinfunction "2_2") (pintype "passive"))
      (node (ref "R3") (pin "1") (pinfunction "1_1") (pintype "passive"))
    )
    (net (code "66") (name "Net-(D2-Pad2)") (class "Default")
      (node (ref "D2") (pin "2") (pinfunction "2_2") (pintype "passive"))
      (node (ref "R4") (pin "1") (pinfunction "1_1") (pintype "passive"))
    )
    (net (code "67") (name "Net-(J1-CC1)") (class "Default")
      (node (ref "J1") (pin "A5") (pinfunction "CC1_A5") (pintype "passive"))
      (node (ref "R12") (pin "2") (pinfunction "2_2") (pintype "passive"))
    )
    (net (code "68") (name "Net-(J1-CC2)") (class "Default")
      (node (ref "J1") (pin "B5") (pinfunction "CC2_B5") (pintype "passive"))
      (node (ref "R11") (pin "2") (pinfunction "2_2") (pintype "passive"))
    )
    (net (code "69") (name "Net-(J4-CC1)") (class "Default")
      (node (ref "J4") (pin "A5") (pinfunction "CC1_A5") (pintype "passive"))
      (node (ref "R15") (pin "2") (pinfunction "2_2") (pintype "passive"))
    )
    (net (code "70") (name "Net-(J4-CC2)") (class "Default")
      (node (ref "J4") (pin "B5") (pinfunction "CC2_B5") (pintype "passive"))
      (node (ref "R14") (pin "2") (pinfunction "2_2") (pintype "passive"))
    )
    (net (code "71") (name "Net-(Q1-B)") (class "Default")
      (node (ref "Q1") (pin "1") (pinfunction "B_1") (pintype "passive"))
      (node (ref "R16") (pin "2") (pinfunction "2_2") (pintype "passive"))
    )
    (net (code "72") (name "Net-(Q2-B)") (class "Default")
      (node (ref "Q2") (pin "1") (pinfunction "B_1") (pintype "passive"))
      (node (ref "R18") (pin "2") (pinfunction "2_2") (pintype "passive"))
    )
    (net (code "73") (name "Net-(U1-CBUS0)") (class "Default")
      (node (ref "R9") (pin "1") (pinfunction "1_1") (pintype "passive"))
      (node (ref "U1") (pin "15") (pinfunction "CBUS0_15") (pintype "passive"))
    )
    (net (code "74") (name "unconnected-(J1-SBU1-PadA8)") (class "Default")
      (node (ref "J1") (pin "A8") (pinfunction "SBU1_A8") (pintype "passive+no_connect"))
    )
    (net (code "75") (name "unconnected-(J1-SBU2-PadB8)") (class "Default")
      (node (ref "J1") (pin "B8") (pinfunction "SBU2_B8") (pintype "passive+no_connect"))
    )
    (net (code "76") (name "unconnected-(J2-Pad24)") (class "Default")
      (node (ref "J2") (pin "24") (pinfunction "24_24") (pintype "passive+no_connect"))
    )
    (net (code "77") (name "unconnected-(J4-SBU1-PadA8)") (class "Default")
      (node (ref "J4") (pin "A8") (pinfunction "SBU1_A8") (pintype "passive+no_connect"))
    )
    (net (code "78") (name "unconnected-(J4-SBU2-PadB8)") (class "Default")
      (node (ref "J4") (pin "B8") (pinfunction "SBU2_B8") (pintype "passive+no_connect"))
    )
    (net (code "79") (name "unconnected-(U1-CBUS1-Pad14)") (class "Default")
      (node (ref "U1") (pin "14") (pinfunction "CBUS1_14") (pintype "passive+no_connect"))
    )
    (net (code "80") (name "unconnected-(U1-CBUS2-Pad7)") (class "Default")
      (node (ref "U1") (pin "7") (pinfunction "CBUS2_7") (pintype "passive+no_connect"))
    )
    (net (code "81") (name "unconnected-(U1-~{CTS}-Pad6)") (class "Default")
      (node (ref "U1") (pin "6") (pinfunction "~{CTS}_6") (pintype "passive+no_connect"))
    )
    (net (code "82") (name "unconnected-(U1-~{DCD}-Pad5)") (class "Default")
      (node (ref "U1") (pin "5") (pinfunction "~{DCD}_5") (pintype "passive+no_connect"))
    )
    (net (code "83") (name "unconnected-(U1-~{DSR}-Pad4)") (class "Default")
      (node (ref "U1") (pin "4") (pinfunction "~{DSR}_4") (pintype "passive+no_connect"))
    )
    (net (code "84") (name "unconnected-(U1-~{RI}-Pad2)") (class "Default")
      (node (ref "U1") (pin "2") (pinfunction "~{RI}_2") (pintype "passive+no_connect"))
    )
  )
)
